# MINI-PCIE.net
KiCad netlist of a schematic drawn in Altium Designer
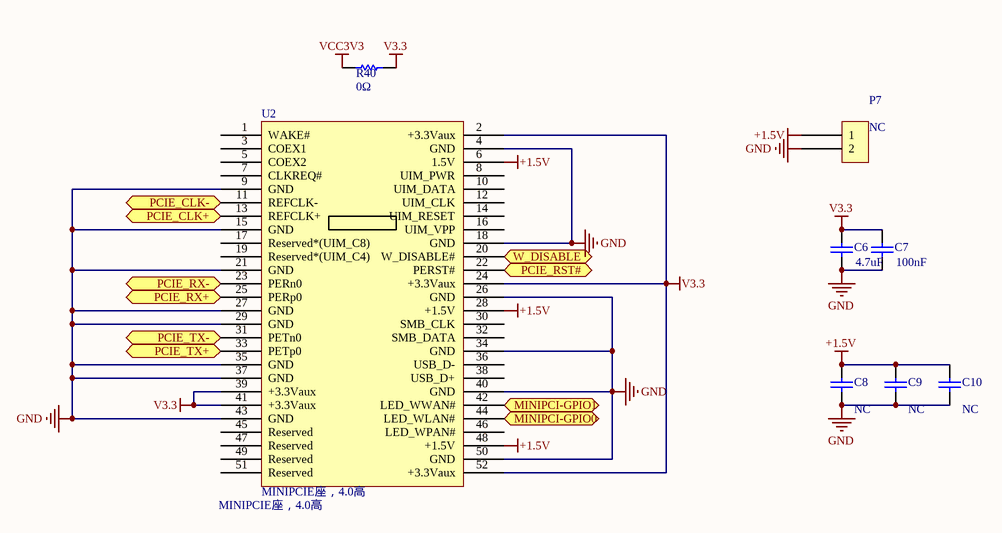
[diagram p0: MINI-PCIE.SchDoc]

(export (version "E")
  (design (tool "Eeschema 10.0.6"))
  (components
    (comp (ref "C6")
      (value "4.7uF")
      (footprint "C0603N")
      (description "Capacitor")
      (fields (field (name "PUBLISHER") "Altium Limited"))
      (libsource (lib "Miscellaneous Devices") (part "Cap"))
    )
    (comp (ref "C7")
      (value "100nF")
      (footprint "0402")
      (description "Capacitor")
      (fields (field (name "PUBLISHER") "Altium Limited"))
      (libsource (lib "Miscellaneous Devices") (part "Cap"))
    )
    (comp (ref "C8")
      (value "NC")
      (footprint "C0603N")
      (description "Capacitor")
      (fields (field (name "PUBLISHER") "Altium Limited"))
      (libsource (lib "Miscellaneous Devices") (part "Cap"))
    )
    (comp (ref "C9")
      (value "NC")
      (footprint "0402")
      (description "Capacitor")
      (fields (field (name "PUBLISHER") "Altium Limited"))
      (libsource (lib "Miscellaneous Devices") (part "Cap"))
    )
    (comp (ref "C10")
      (value "NC")
      (footprint "0402")
      (description "Capacitor")
      (fields (field (name "PUBLISHER") "Altium Limited"))
      (libsource (lib "Miscellaneous Devices") (part "Cap"))
    )
    (comp (ref "P7") (value "NC") (footprint "HDR1X2") (libsource (lib "Interface") (part "Head2")))
    (comp (ref "R40")
      (value "0Ω")
      (footprint "R0805N")
      (description "Semiconductor Resistor")
      (fields (field (name "PUBLISHER") "Altium Limited"))
      (libsource (lib "Miscellaneous Devices") (part "Res Semi"))
    )
    (comp (ref "U2")
      (value "MINIPCIE座，4.0高")
      (footprint "MINIPCIE")
      (fields (field (name "ALTIUM_VALUE") "MINIPCIE座，4.0高"))
      (libsource (lib "Interface") (part "PCI-E MINI CARD CONNECTOR"))
    )
  )
  (nets
    (net (code "1") (name "+1.5V") (class "Default")
      (node (ref "C10") (pin "2") (pinfunction "2_2") (pintype "passive"))
      (node (ref "C8") (pin "2") (pinfunction "2_2") (pintype "passive"))
      (node (ref "C9") (pin "2") (pinfunction "2_2") (pintype "passive"))
      (node (ref "P7") (pin "1") (pinfunction "1_1") (pintype "passive"))
      (node (ref "U2") (pin "28") (pinfunction "+1.5V_28") (pintype "passive"))
      (node (ref "U2") (pin "48") (pinfunction "+1.5V_48") (pintype "passive"))
      (node (ref "U2") (pin "6") (pinfunction "1.5V_6") (pintype "passive"))
    )
    (net (code "2") (name "/MINIPCI-GPIO0") (class "Default")
      (node (ref "U2") (pin "44") (pinfunction "LED_WLAN#_44") (pintype "passive"))
    )
    (net (code "3") (name "/MINIPCI-GPIO1") (class "Default")
      (node (ref "U2") (pin "42") (pinfunction "LED_WWAN#_42") (pintype "passive"))
    )
    (net (code "4") (name "/PCIE_CLK+") (class "Default")
      (node (ref "U2") (pin "13") (pinfunction "REFCLK+_13") (pintype "passive"))
    )
    (net (code "5") (name "/PCIE_CLK-") (class "Default")
      (node (ref "U2") (pin "11") (pinfunction "REFCLK-_11") (pintype "passive"))
    )
    (net (code "6") (name "/PCIE_RST#") (class "Default")
      (node (ref "U2") (pin "22") (pinfunction "PERST#_22") (pintype "passive"))
    )
    (net (code "7") (name "/PCIE_RX+") (class "Default")
      (node (ref "U2") (pin "25") (pinfunction "PERp0_25") (pintype "passive"))
    )
    (net (code "8") (name "/PCIE_RX-") (class "Default")
      (node (ref "U2") (pin "23") (pinfunction "PERn0_23") (pintype "passive"))
    )
    (net (code "9") (name "/PCIE_TX+") (class "Default")
      (node (ref "U2") (pin "33") (pinfunction "PETp0_33") (pintype "passive"))
    )
    (net (code "10") (name "/PCIE_TX-") (class "Default")
      (node (ref "U2") (pin "31") (pinfunction "PETn0_31") (pintype "passive"))
    )
    (net (code "11") (name "/W_DISABLE") (class "Default")
      (node (ref "U2") (pin "20") (pinfunction "W_DISABLE#_20") (pintype "passive"))
    )
    (net (code "12") (name "GND") (class "Default")
      (node (ref "C10") (pin "1") (pinfunction "1_1") (pintype "passive"))
      (node (ref "C6") (pin "1") (pinfunction "1_1") (pintype "passive"))
      (node (ref "C7") (pin "1") (pinfunction "1_1") (pintype "passive"))
      (node (ref "C8") (pin "1") (pinfunction "1_1") (pintype "passive"))
      (node (ref "C9") (pin "1") (pinfunction "1_1") (pintype "passive"))
      (node (ref "P7") (pin "2") (pinfunction "2_2") (pintype "passive"))
      (node (ref "U2") (pin "15") (pinfunction "GND_15") (pintype "passive"))
      (node (ref "U2") (pin "18") (pinfunction "GND_18") (pintype "passive"))
      (node (ref "U2") (pin "21") (pinfunction "GND_21") (pintype "passive"))
      (node (ref "U2") (pin "26") (pinfunction "GND_26") (pintype "passive"))
      (node (ref "U2") (pin "27") (pinfunction "GND_27") (pintype "passive"))
      (node (ref "U2") (pin "29") (pinfunction "GND_29") (pintype "passive"))
      (node (ref "U2") (pin "34") (pinfunction "GND_34") (pintype "passive"))
      (node (ref "U2") (pin "35") (pinfunction "GND_35") (pintype "passive"))
      (node (ref "U2") (pin "37") (pinfunction "GND_37") (pintype "passive"))
      (node (ref "U2") (pin "4") (pinfunction "GND_4") (pintype "passive"))
      (node (ref "U2") (pin "40") (pinfunction "GND_40") (pintype "passive"))
      (node (ref "U2") (pin "43") (pinfunction "GND_43") (pintype "passive"))
      (node (ref "U2") (pin "50") (pinfunction "GND_50") (pintype "passive"))
      (node (ref "U2") (pin "9") (pinfunction "GND_9") (pintype "passive"))
    )
    (net (code "13") (name "V3.3") (class "Default")
      (node (ref "C6") (pin "2") (pinfunction "2_2") (pintype "passive"))
      (node (ref "C7") (pin "2") (pinfunction "2_2") (pintype "passive"))
      (node (ref "R40") (pin "1") (pinfunction "1_1") (pintype "passive"))
      (node (ref "U2") (pin "2") (pinfunction "+3.3Vaux_2") (pintype "passive"))
      (node (ref "U2") (pin "24") (pinfunction "+3.3Vaux_24") (pintype "passive"))
      (node (ref "U2") (pin "39") (pinfunction "+3.3Vaux_39") (pintype "passive"))
      (node (ref "U2") (pin "41") (pinfunction "+3.3Vaux_41") (pintype "passive"))
      (node (ref "U2") (pin "52") (pinfunction "+3.3Vaux_52") (pintype "passive"))
    )
    (net (code "14") (name "VCC3V3") (class "Default")
      (node (ref "R40") (pin "2") (pinfunction "2_2") (pintype "passive"))
    )
    (net (code "15") (name "unconnected-(U2-CLKREQ#-Pad7)") (class "Default")
      (node (ref "U2") (pin "7") (pinfunction "CLKREQ#_7") (pintype "passive"))
    )
    (net (code "16") (name "unconnected-(U2-COEX1-Pad3)") (class "Default")
      (node (ref "U2") (pin "3") (pinfunction "COEX1_3") (pintype "passive"))
    )
    (net (code "17") (name "unconnected-(U2-COEX2-Pad5)") (class "Default")
      (node (ref "U2") (pin "5") (pinfunction "COEX2_5") (pintype "passive"))
    )
    (net (code "18") (name "unconnected-(U2-LED_WPAN#-Pad46)") (class "Default")
      (node (ref "U2") (pin "46") (pinfunction "LED_WPAN#_46") (pintype "passive"))
    )
    (net (code "19") (name "unconnected-(U2-Reserved*(UIM_C4)-Pad19)") (class "Default")
      (node (ref "U2") (pin "19") (pinfunction "Reserved*(UIM_C4)_19") (pintype "passive"))
    )
    (net (code "20") (name "unconnected-(U2-Reserved*(UIM_C8)-Pad17)") (class "Default")
      (node (ref "U2") (pin "17") (pinfunction "Reserved*(UIM_C8)_17") (pintype "passive"))
    )
    (net (code "21") (name "unconnected-(U2-Reserved-Pad45)") (class "Default")
      (node (ref "U2") (pin "45") (pinfunction "Reserved_45") (pintype "passive"))
    )
    (net (code "22") (name "unconnected-(U2-Reserved-Pad47)") (class "Default")
      (node (ref "U2") (pin "47") (pinfunction "Reserved_47") (pintype "passive"))
    )
    (net (code "23") (name "unconnected-(U2-Reserved-Pad49)") (class "Default")
      (node (ref "U2") (pin "49") (pinfunction "Reserved_49") (pintype "passive"))
    )
    (net (code "24") (name "unconnected-(U2-Reserved-Pad51)") (class "Default")
      (node (ref "U2") (pin "51") (pinfunction "Reserved_51") (pintype "passive"))
    )
    (net (code "25") (name "unconnected-(U2-SMB_CLK-Pad30)") (class "Default")
      (node (ref "U2") (pin "30") (pinfunction "SMB_CLK_30") (pintype "passive"))
    )
    (net (code "26") (name "unconnected-(U2-SMB_DATA-Pad32)") (class "Default")
      (node (ref "U2") (pin "32") (pinfunction "SMB_DATA_32") (pintype "passive"))
    )
    (net (code "27") (name "unconnected-(U2-UIM_CLK-Pad12)") (class "Default")
      (node (ref "U2") (pin "12") (pinfunction "UIM_CLK_12") (pintype "passive"))
    )
    (net (code "28") (name "unconnected-(U2-UIM_DATA-Pad10)") (class "Default")
      (node (ref "U2") (pin "10") (pinfunction "UIM_DATA_10") (pintype "passive"))
    )
    (net (code "29") (name "unconnected-(U2-UIM_PWR-Pad8)") (class "Default")
      (node (ref "U2") (pin "8") (pinfunction "UIM_PWR_8") (pintype "passive"))
    )
    (net (code "30") (name "unconnected-(U2-UIM_RESET-Pad14)") (class "Default")
      (node (ref "U2") (pin "14") (pinfunction "UIM_RESET_14") (pintype "passive"))
    )
    (net (code "31") (name "unconnected-(U2-UIM_VPP-Pad16)") (class "Default")
      (node (ref "U2") (pin "16") (pinfunction "UIM_VPP_16") (pintype "passive"))
    )
    (net (code "32") (name "unconnected-(U2-USB_D+-Pad38)") (class "Default")
      (node (ref "U2") (pin "38") (pinfunction "USB_D+_38") (pintype "passive"))
    )
    (net (code "33") (name "unconnected-(U2-USB_D--Pad36)") (class "Default")
      (node (ref "U2") (pin "36") (pinfunction "USB_D-_36") (pintype "passive"))
    )
    (net (code "34") (name "unconnected-(U2-WAKE#-Pad1)") (class "Default")
      (node (ref "U2") (pin "1") (pinfunction "WAKE#_1") (pintype "passive"))
    )
  )
)
